# design.net
KiCad netlist of a schematic drawn in EasyEDA
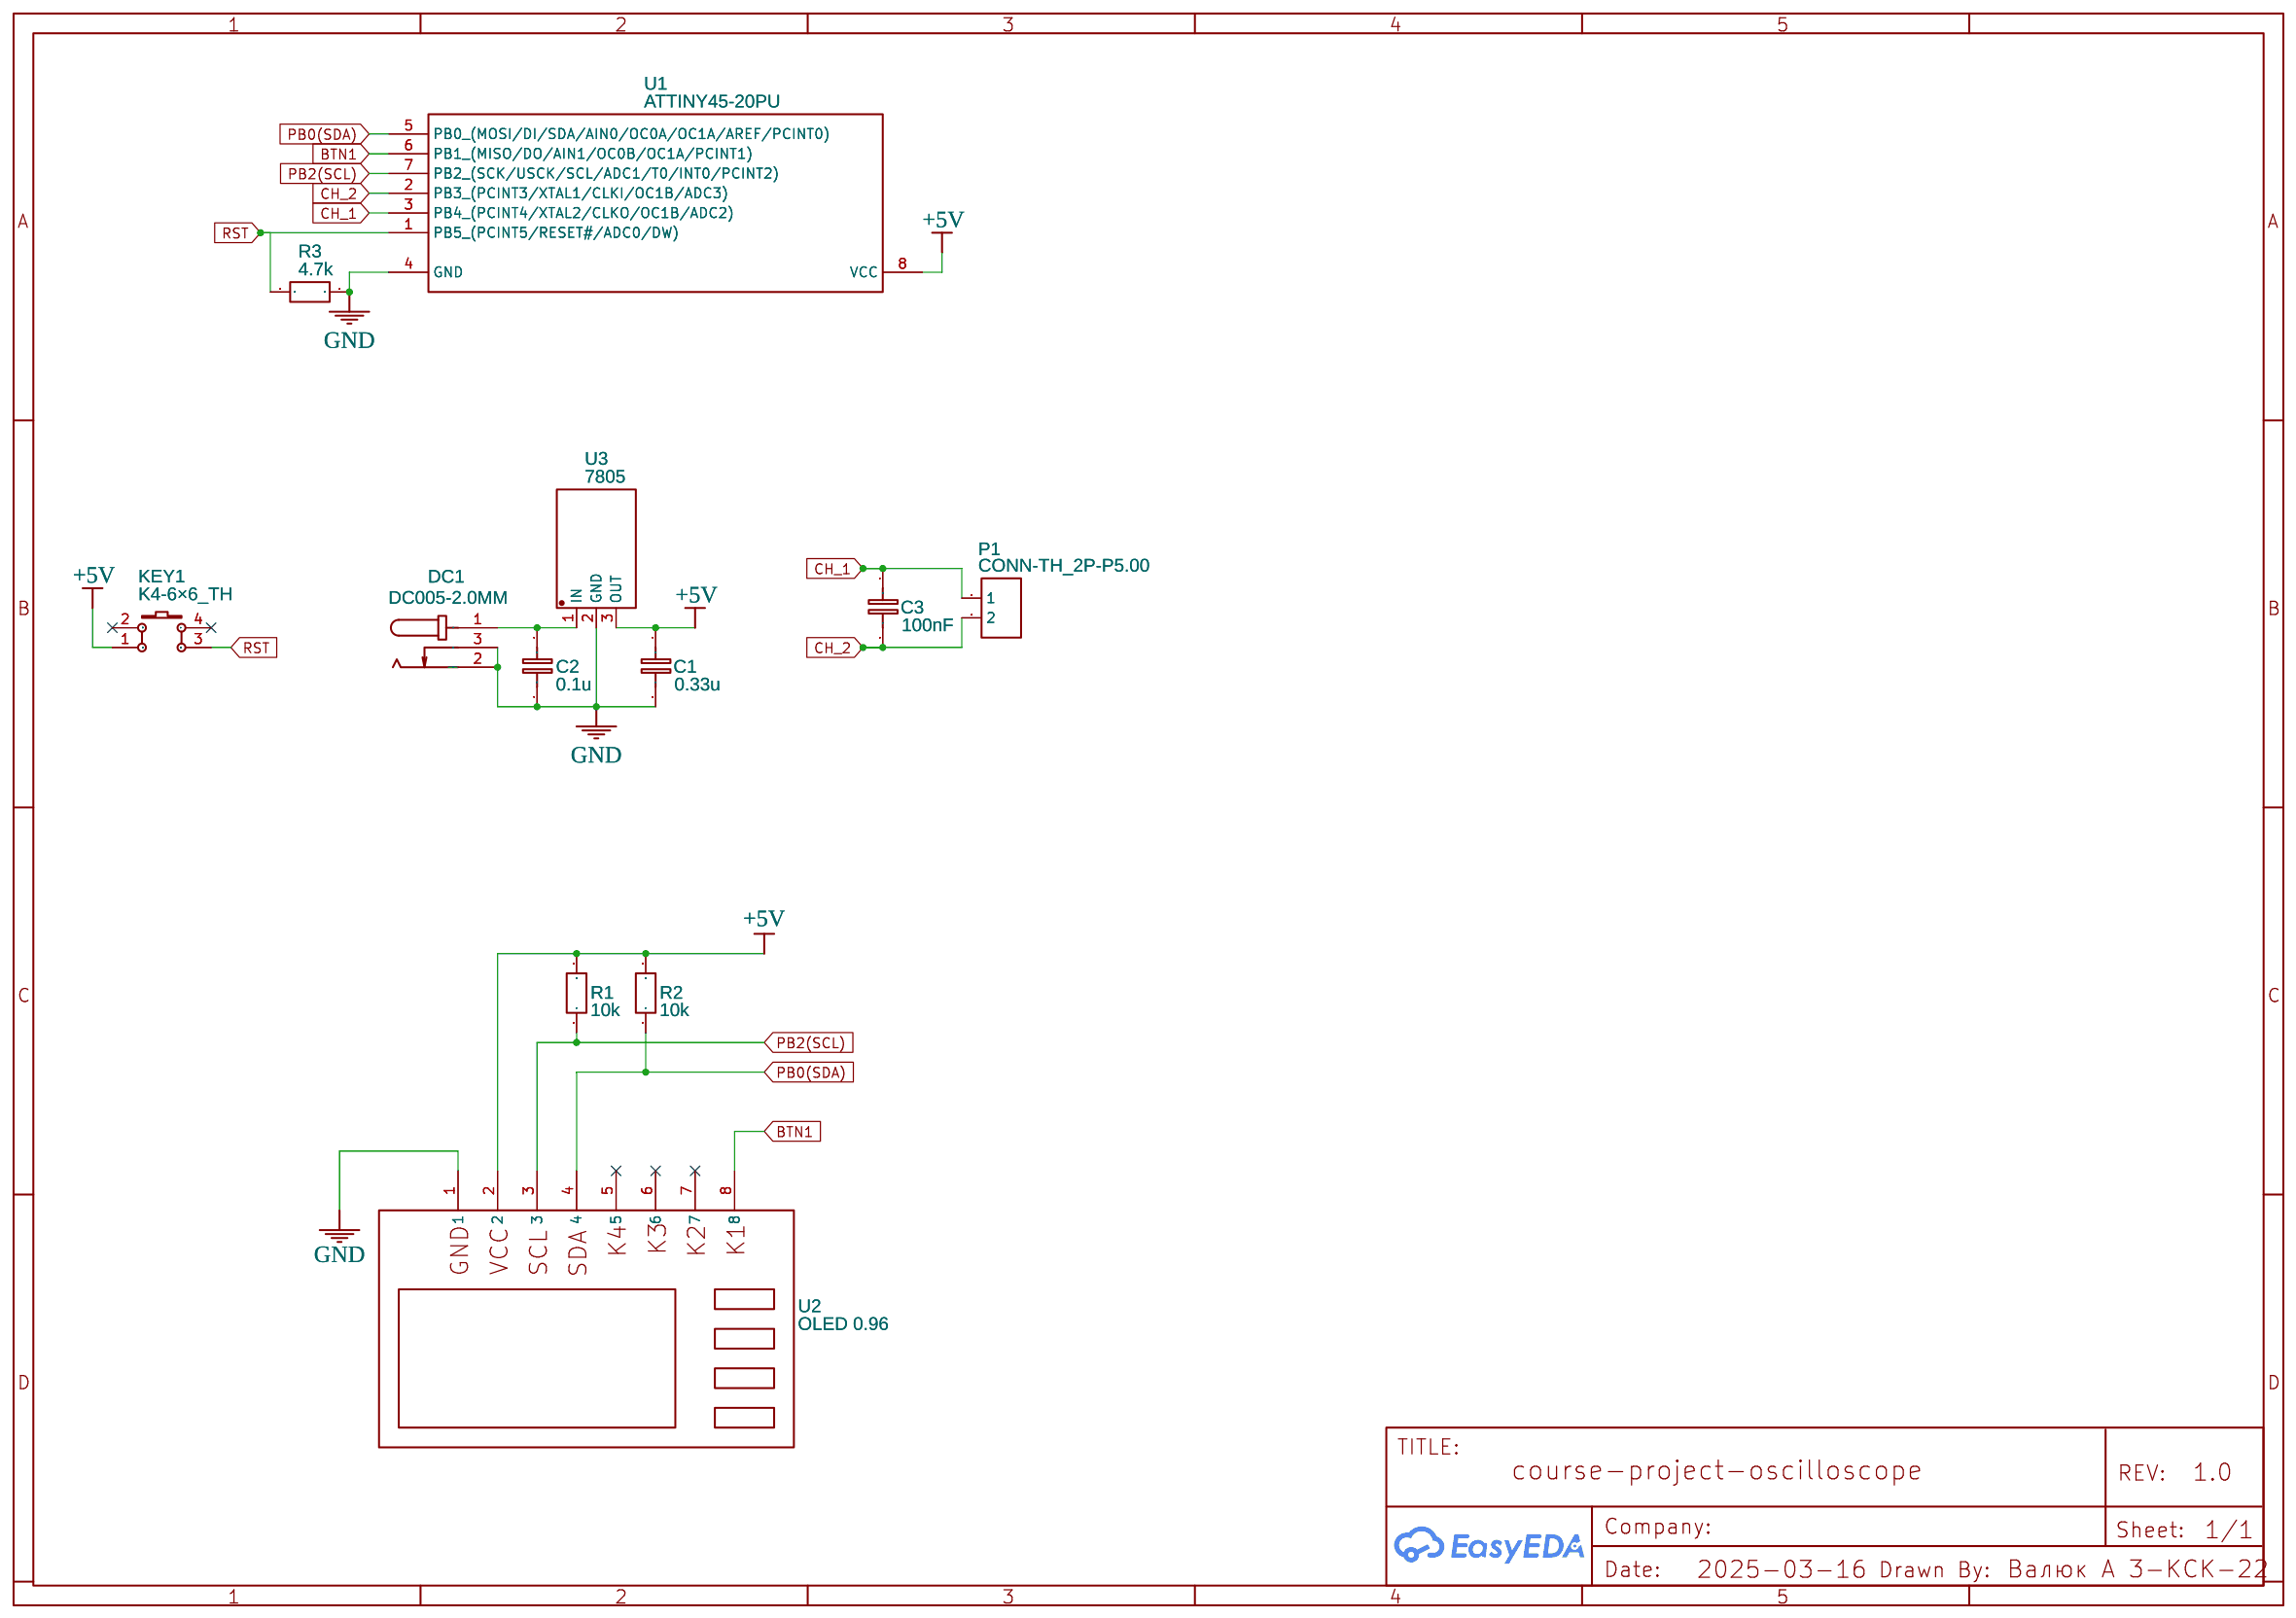
[diagram p0: oscilloscope]
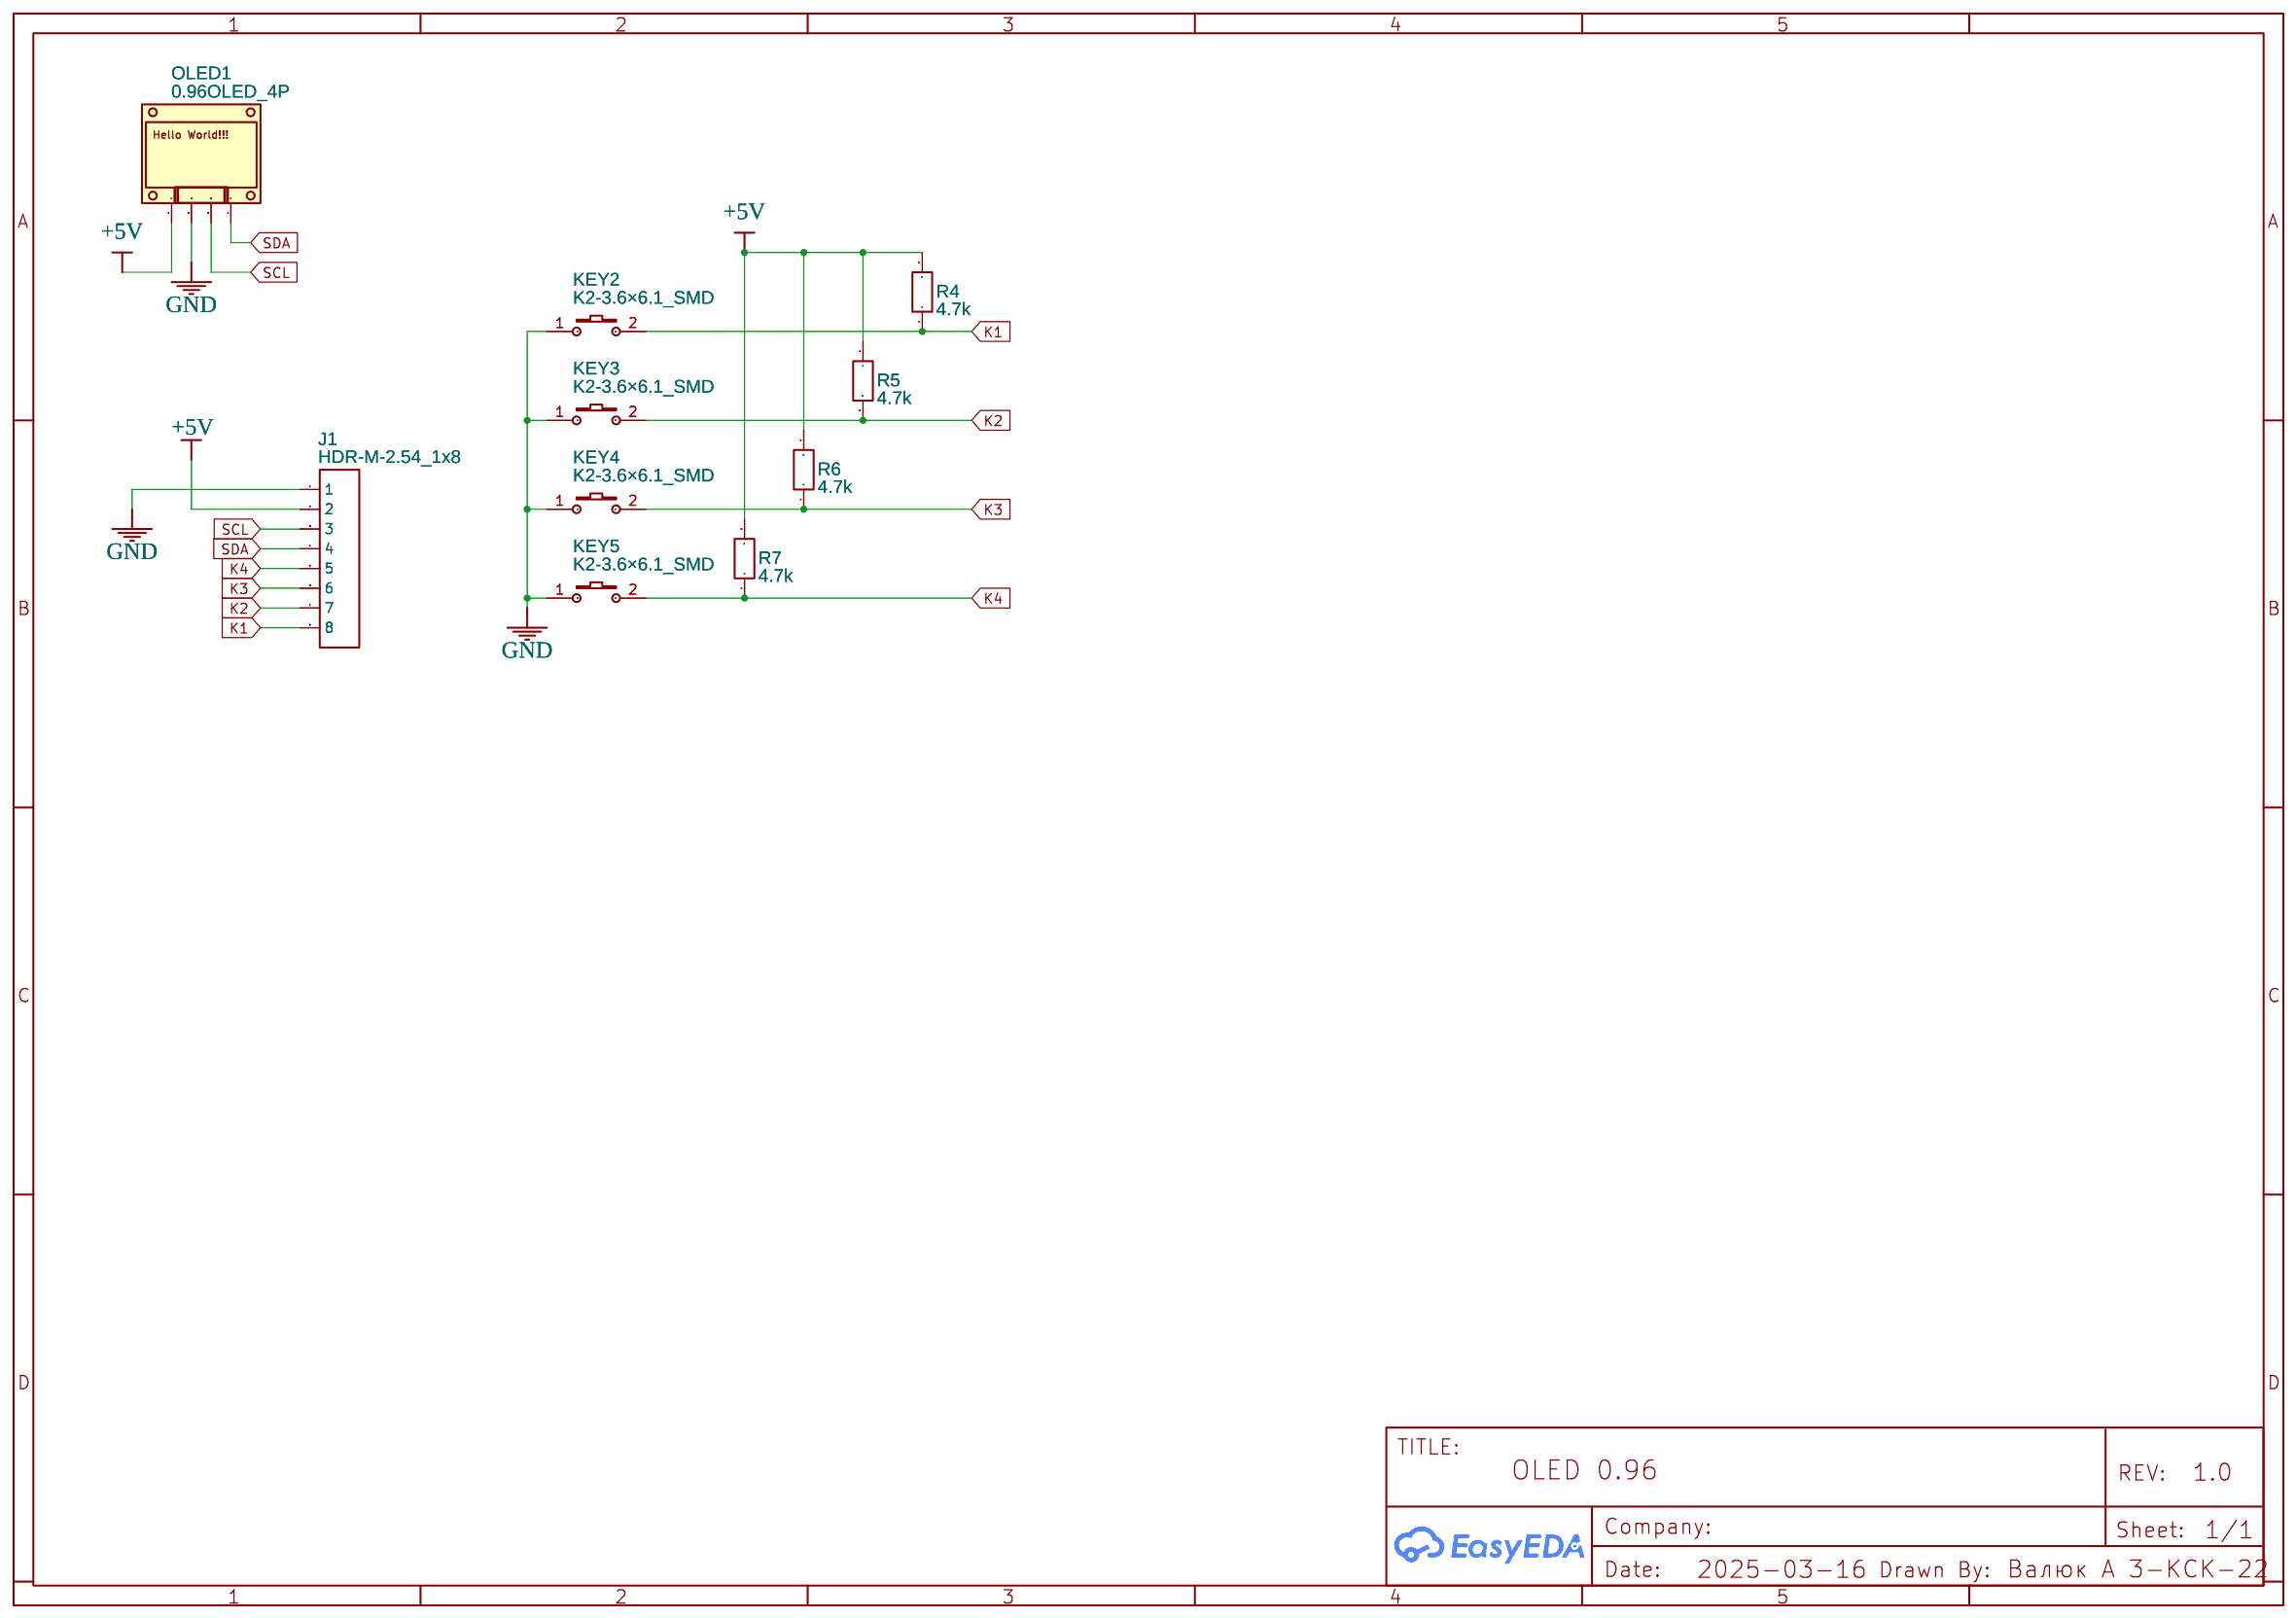
[diagram p1: OLED]

(export (version "E")
  (design (tool "Eeschema 10.0.6"))
  (components
    (comp (ref "C1") (value "0.33u") (libsource (lib "") (part "C_RAD-0.1_EU")))
    (comp (ref "C2") (value "0.1u") (libsource (lib "") (part "C_RAD-0.1_EU")))
    (comp (ref "C3") (value "100nF") (libsource (lib "") (part "C_RAD-0.1_EU")))
    (comp (ref "DC1")
      (value "DC005-2.0MM")
      (fields (field (name "Manufacturer") "SOFNG"))
      (libsource (lib "") (part "DC005-2.0MM"))
    )
    (comp (ref "KEY1")
      (value "K4-6×6_TH")
      (fields (field (name "Manufacturer Part") "K2-1102DP-E4SW-04") (field (name "Manufacturer") "韩国韩荣"))
      (libsource (lib "") (part "K4-6×6_TH"))
    )
    (comp (ref "P1") (value "CONN-TH_2P-P5.00") (libsource (lib "") (part "CONN-TH_2P-P5.00")))
    (comp (ref "R1") (value "10k") (libsource (lib "") (part "R_AXIAL-0.3_EU")))
    (comp (ref "R2") (value "10k") (libsource (lib "") (part "R_AXIAL-0.3_EU")))
    (comp (ref "R3") (value "4.7k") (libsource (lib "") (part "R_AXIAL-0.3_EU_1")))
    (comp (ref "U1")
      (value "ATTINY45-20PU")
      (fields (field (name "Manufacturer") "MICROCHIP(美国微芯)"))
      (libsource (lib "") (part "ATTINY45-20PU"))
    )
    (comp (ref "U2") (value "OLED 0.96") (libsource (lib "") (part "OLED 0.96")))
    (comp (ref "U3")
      (value "7805")
      (fields (field (name "Manufacturer") "BLUE ROCKET(蓝箭)"))
      (libsource (lib "") (part "7805"))
    )
    (comp (ref "J1") (value "HDR-M-2.54_1x8") (libsource (lib "") (part "HDR-M-2.54_1x8")))
    (comp (ref "KEY2")
      (value "K2-3.6×6.1_SMD")
      (fields (field (name "Manufacturer Part") "K2-1107ST-A4SW-06"))
      (libsource (lib "") (part "K2-3.6×6.1_SMD"))
    )
    (comp (ref "KEY3")
      (value "K2-3.6×6.1_SMD")
      (fields (field (name "Manufacturer Part") "K2-1107ST-A4SW-06"))
      (libsource (lib "") (part "K2-3.6×6.1_SMD"))
    )
    (comp (ref "KEY4")
      (value "K2-3.6×6.1_SMD")
      (fields (field (name "Manufacturer Part") "K2-1107ST-A4SW-06"))
      (libsource (lib "") (part "K2-3.6×6.1_SMD"))
    )
    (comp (ref "KEY5")
      (value "K2-3.6×6.1_SMD")
      (fields (field (name "Manufacturer Part") "K2-1107ST-A4SW-06"))
      (libsource (lib "") (part "K2-3.6×6.1_SMD"))
    )
    (comp (ref "OLED1") (value "0.96OLED_4P") (libsource (lib "") (part "0.96OLED_4P")))
    (comp (ref "R4") (value "4.7k") (libsource (lib "") (part "R_0603_EU_1")))
    (comp (ref "R5") (value "4.7k") (libsource (lib "") (part "R_0603_EU")))
    (comp (ref "R6") (value "4.7k") (libsource (lib "") (part "R_0603_EU_1")))
    (comp (ref "R7") (value "4.7k") (libsource (lib "") (part "R_0603_EU_1")))
  )
  (nets
    (net (code "1") (name "+5V") (class "Default")
      (node (ref "C1") (pin "1") (pinfunction "1_1") (pintype "unspecified"))
      (node (ref "J1") (pin "2") (pinfunction "2_2") (pintype "unspecified"))
      (node (ref "KEY1") (pin "1") (pinfunction "1_1") (pintype "unspecified"))
      (node (ref "OLED1") (pin "1") (pinfunction "1_1") (pintype "unspecified"))
      (node (ref "R1") (pin "2") (pinfunction "2_2") (pintype "unspecified"))
      (node (ref "R2") (pin "2") (pinfunction "2_2") (pintype "unspecified"))
      (node (ref "R4") (pin "2") (pinfunction "2_2") (pintype "unspecified"))
      (node (ref "R5") (pin "1") (pinfunction "1_1") (pintype "unspecified"))
      (node (ref "R6") (pin "2") (pinfunction "2_2") (pintype "unspecified"))
      (node (ref "R7") (pin "2") (pinfunction "2_2") (pintype "unspecified"))
      (node (ref "U1") (pin "8") (pinfunction "VCC_8") (pintype "passive"))
      (node (ref "U2") (pin "2") (pinfunction "2_2") (pintype "unspecified"))
      (node (ref "U3") (pin "3") (pinfunction "OUT_3") (pintype "unspecified"))
    )
    (net (code "2") (name "BTN1") (class "Default")
      (node (ref "U1") (pin "6") (pinfunction "PB1_(MISO/DO/AIN1/OC0B/OC1A/PCINT1)_6") (pintype "bidirectional"))
      (node (ref "U2") (pin "8") (pinfunction "8_8") (pintype "unspecified"))
    )
    (net (code "3") (name "CH_1") (class "Default")
      (node (ref "C3") (pin "1") (pinfunction "1_1") (pintype "unspecified"))
      (node (ref "P1") (pin "1") (pinfunction "1_1") (pintype "unspecified"))
      (node (ref "U1") (pin "3") (pinfunction "PB4_(PCINT4/XTAL2/CLKO/OC1B/ADC2)_3") (pintype "bidirectional"))
    )
    (net (code "4") (name "CH_2") (class "Default")
      (node (ref "C3") (pin "2") (pinfunction "2_2") (pintype "unspecified"))
      (node (ref "P1") (pin "2") (pinfunction "2_2") (pintype "unspecified"))
      (node (ref "U1") (pin "2") (pinfunction "PB3_(PCINT3/XTAL1/CLKI/OC1B/ADC3)_2") (pintype "bidirectional"))
    )
    (net (code "5") (name "GND") (class "Default")
      (node (ref "C1") (pin "2") (pinfunction "2_2") (pintype "unspecified"))
      (node (ref "C2") (pin "2") (pinfunction "2_2") (pintype "unspecified"))
      (node (ref "DC1") (pin "2") (pinfunction "2_2") (pintype "unspecified"))
      (node (ref "DC1") (pin "3") (pinfunction "3_3") (pintype "unspecified"))
      (node (ref "J1") (pin "1") (pinfunction "1_1") (pintype "unspecified"))
      (node (ref "KEY2") (pin "1") (pinfunction "1_1") (pintype "unspecified"))
      (node (ref "KEY3") (pin "1") (pinfunction "1_1") (pintype "unspecified"))
      (node (ref "KEY4") (pin "1") (pinfunction "1_1") (pintype "unspecified"))
      (node (ref "KEY5") (pin "1") (pinfunction "1_1") (pintype "unspecified"))
      (node (ref "OLED1") (pin "2") (pinfunction "2_2") (pintype "unspecified"))
      (node (ref "R3") (pin "1") (pinfunction "1_1") (pintype "unspecified"))
      (node (ref "U1") (pin "4") (pinfunction "GND_4") (pintype "passive"))
      (node (ref "U2") (pin "1") (pinfunction "1_1") (pintype "unspecified"))
      (node (ref "U3") (pin "2") (pinfunction "GND_2") (pintype "unspecified"))
    )
    (net (code "6") (name "K1") (class "Default")
      (node (ref "J1") (pin "8") (pinfunction "8_8") (pintype "unspecified"))
      (node (ref "KEY2") (pin "2") (pinfunction "2_2") (pintype "unspecified"))
      (node (ref "R4") (pin "1") (pinfunction "1_1") (pintype "unspecified"))
    )
    (net (code "7") (name "K2") (class "Default")
      (node (ref "J1") (pin "7") (pinfunction "7_7") (pintype "unspecified"))
      (node (ref "KEY3") (pin "2") (pinfunction "2_2") (pintype "unspecified"))
      (node (ref "R5") (pin "2") (pinfunction "2_2") (pintype "unspecified"))
    )
    (net (code "8") (name "K3") (class "Default")
      (node (ref "J1") (pin "6") (pinfunction "6_6") (pintype "unspecified"))
      (node (ref "KEY4") (pin "2") (pinfunction "2_2") (pintype "unspecified"))
      (node (ref "R6") (pin "1") (pinfunction "1_1") (pintype "unspecified"))
    )
    (net (code "9") (name "K4") (class "Default")
      (node (ref "J1") (pin "5") (pinfunction "5_5") (pintype "unspecified"))
      (node (ref "KEY5") (pin "2") (pinfunction "2_2") (pintype "unspecified"))
      (node (ref "R7") (pin "1") (pinfunction "1_1") (pintype "unspecified"))
    )
    (net (code "10") (name "Net-(U3-IN)") (class "Default")
      (node (ref "C2") (pin "1") (pinfunction "1_1") (pintype "unspecified"))
      (node (ref "DC1") (pin "1") (pinfunction "1_1") (pintype "unspecified"))
      (node (ref "U3") (pin "1") (pinfunction "IN_1") (pintype "unspecified"))
    )
    (net (code "11") (name "PB0(SDA)") (class "Default")
      (node (ref "R2") (pin "1") (pinfunction "1_1") (pintype "unspecified"))
      (node (ref "U1") (pin "5") (pinfunction "PB0_(MOSI/DI/SDA/AIN0/OC0A/OC1A/AREF/PCINT0)_5") (pintype "bidirectional"))
      (node (ref "U2") (pin "4") (pinfunction "4_4") (pintype "unspecified"))
    )
    (net (code "12") (name "PB2(SCL)") (class "Default")
      (node (ref "R1") (pin "1") (pinfunction "1_1") (pintype "unspecified"))
      (node (ref "U1") (pin "7") (pinfunction "PB2_(SCK/USCK/SCL/ADC1/T0/INT0/PCINT2)_7") (pintype "bidirectional"))
      (node (ref "U2") (pin "3") (pinfunction "3_3") (pintype "unspecified"))
    )
    (net (code "13") (name "RST") (class "Default")
      (node (ref "KEY1") (pin "3") (pinfunction "3_3") (pintype "unspecified"))
      (node (ref "R3") (pin "2") (pinfunction "2_2") (pintype "unspecified"))
      (node (ref "U1") (pin "1") (pinfunction "PB5_(PCINT5/RESET#/ADC0/DW)_1") (pintype "bidirectional"))
    )
    (net (code "14") (name "SCL") (class "Default")
      (node (ref "J1") (pin "3") (pinfunction "3_3") (pintype "unspecified"))
      (node (ref "OLED1") (pin "3") (pinfunction "3_3") (pintype "unspecified"))
    )
    (net (code "15") (name "SDA") (class "Default")
      (node (ref "J1") (pin "4") (pinfunction "4_4") (pintype "unspecified"))
      (node (ref "OLED1") (pin "4") (pinfunction "4_4") (pintype "unspecified"))
    )
    (net (code "16") (name "unconnected-(KEY1-Pad2)") (class "Default")
      (node (ref "KEY1") (pin "2") (pinfunction "2_2") (pintype "unspecified+no_connect"))
    )
    (net (code "17") (name "unconnected-(KEY1-Pad4)") (class "Default")
      (node (ref "KEY1") (pin "4") (pinfunction "4_4") (pintype "unspecified+no_connect"))
    )
    (net (code "18") (name "unconnected-(U2-Pad5)") (class "Default")
      (node (ref "U2") (pin "5") (pinfunction "5_5") (pintype "unspecified+no_connect"))
    )
    (net (code "19") (name "unconnected-(U2-Pad6)") (class "Default")
      (node (ref "U2") (pin "6") (pinfunction "6_6") (pintype "unspecified+no_connect"))
    )
    (net (code "20") (name "unconnected-(U2-Pad7)") (class "Default")
      (node (ref "U2") (pin "7") (pinfunction "7_7") (pintype "unspecified+no_connect"))
    )
  )
)
